# LED.net
KiCad netlist of a schematic drawn in EAGLE
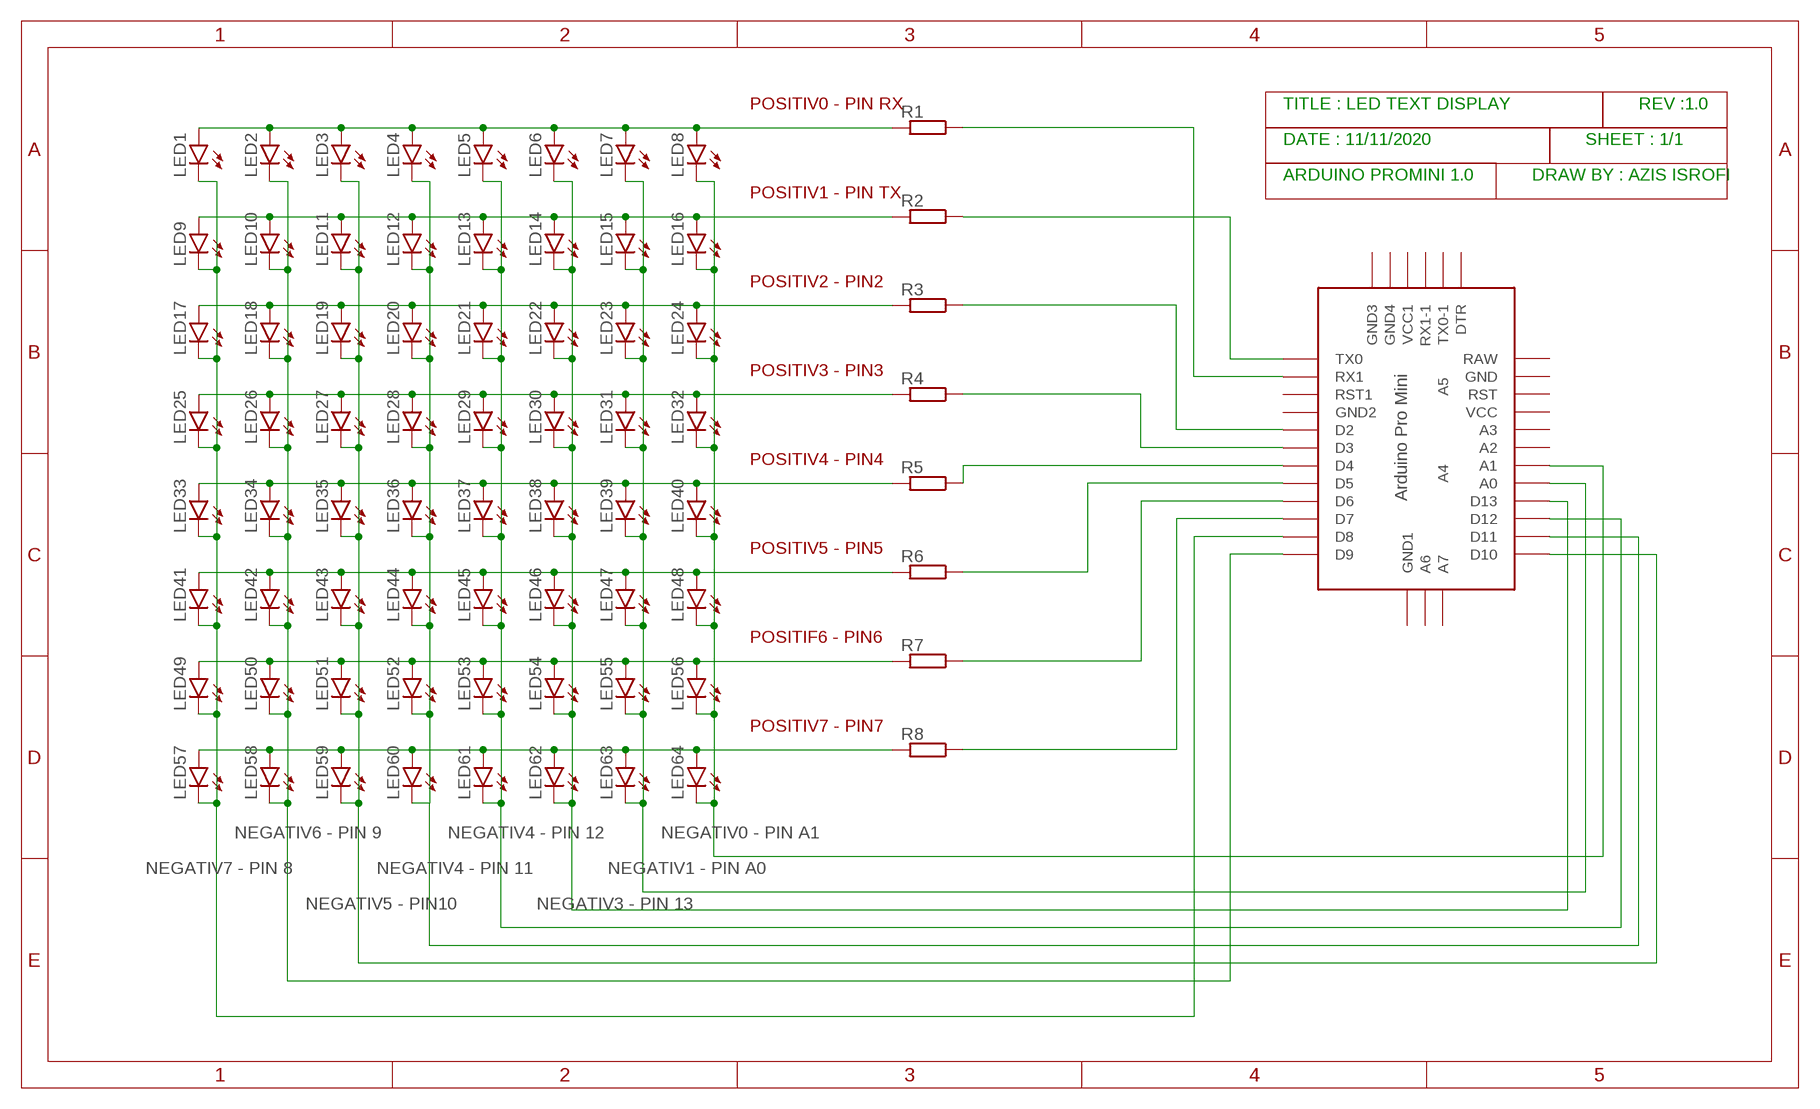
[diagram p0: schematic, sheet 1]

(export (version "E")
  (design (tool "Eeschema 10.0.6"))
  (components
    (comp (ref "LED1")
      (value "LED")
      (footprint "eagle-import:SMARTLED-TTW")
      (libsource (lib "eagle-import") (part "LED"))
    )
    (comp (ref "LED2")
      (value "LED")
      (footprint "eagle-import:SMARTLED-TTW")
      (libsource (lib "eagle-import") (part "LED"))
    )
    (comp (ref "LED3")
      (value "LED")
      (footprint "eagle-import:SMARTLED-TTW")
      (libsource (lib "eagle-import") (part "LED"))
    )
    (comp (ref "LED4")
      (value "LED")
      (footprint "eagle-import:SMARTLED-TTW")
      (libsource (lib "eagle-import") (part "LED"))
    )
    (comp (ref "LED5")
      (value "LED")
      (footprint "eagle-import:SMARTLED-TTW")
      (libsource (lib "eagle-import") (part "LED"))
    )
    (comp (ref "LED6")
      (value "LED")
      (footprint "eagle-import:SMARTLED-TTW")
      (libsource (lib "eagle-import") (part "LED"))
    )
    (comp (ref "LED7")
      (value "LED")
      (footprint "eagle-import:SMARTLED-TTW")
      (libsource (lib "eagle-import") (part "LED"))
    )
    (comp (ref "LED8")
      (value "LED")
      (footprint "eagle-import:SMARTLED-TTW")
      (libsource (lib "eagle-import") (part "LED"))
    )
    (comp (ref "LED9")
      (value "LED")
      (footprint "eagle-import:SMARTLED-TTW")
      (libsource (lib "eagle-import") (part "LED"))
    )
    (comp (ref "LED10")
      (value "LED")
      (footprint "eagle-import:SMARTLED-TTW")
      (libsource (lib "eagle-import") (part "LED"))
    )
    (comp (ref "LED11")
      (value "LED")
      (footprint "eagle-import:SMARTLED-TTW")
      (libsource (lib "eagle-import") (part "LED"))
    )
    (comp (ref "LED12")
      (value "LED")
      (footprint "eagle-import:SMARTLED-TTW")
      (libsource (lib "eagle-import") (part "LED"))
    )
    (comp (ref "LED13")
      (value "LED")
      (footprint "eagle-import:SMARTLED-TTW")
      (libsource (lib "eagle-import") (part "LED"))
    )
    (comp (ref "LED14")
      (value "LED")
      (footprint "eagle-import:SMARTLED-TTW")
      (libsource (lib "eagle-import") (part "LED"))
    )
    (comp (ref "LED15")
      (value "LED")
      (footprint "eagle-import:SMARTLED-TTW")
      (libsource (lib "eagle-import") (part "LED"))
    )
    (comp (ref "LED16")
      (value "LED")
      (footprint "eagle-import:SMARTLED-TTW")
      (libsource (lib "eagle-import") (part "LED"))
    )
    (comp (ref "LED17")
      (value "LED")
      (footprint "eagle-import:SMARTLED-TTW")
      (libsource (lib "eagle-import") (part "LED"))
    )
    (comp (ref "LED18")
      (value "LED")
      (footprint "eagle-import:SMARTLED-TTW")
      (libsource (lib "eagle-import") (part "LED"))
    )
    (comp (ref "LED19")
      (value "LED")
      (footprint "eagle-import:SMARTLED-TTW")
      (libsource (lib "eagle-import") (part "LED"))
    )
    (comp (ref "LED20")
      (value "LED")
      (footprint "eagle-import:SMARTLED-TTW")
      (libsource (lib "eagle-import") (part "LED"))
    )
    (comp (ref "LED21")
      (value "LED")
      (footprint "eagle-import:SMARTLED-TTW")
      (libsource (lib "eagle-import") (part "LED"))
    )
    (comp (ref "LED22")
      (value "LED")
      (footprint "eagle-import:SMARTLED-TTW")
      (libsource (lib "eagle-import") (part "LED"))
    )
    (comp (ref "LED23")
      (value "LED")
      (footprint "eagle-import:SMARTLED-TTW")
      (libsource (lib "eagle-import") (part "LED"))
    )
    (comp (ref "LED24")
      (value "LED")
      (footprint "eagle-import:SMARTLED-TTW")
      (libsource (lib "eagle-import") (part "LED"))
    )
    (comp (ref "LED25")
      (value "LED")
      (footprint "eagle-import:SMARTLED-TTW")
      (libsource (lib "eagle-import") (part "LED"))
    )
    (comp (ref "LED26")
      (value "LED")
      (footprint "eagle-import:SMARTLED-TTW")
      (libsource (lib "eagle-import") (part "LED"))
    )
    (comp (ref "LED27")
      (value "LED")
      (footprint "eagle-import:SMARTLED-TTW")
      (libsource (lib "eagle-import") (part "LED"))
    )
    (comp (ref "LED28")
      (value "LED")
      (footprint "eagle-import:SMARTLED-TTW")
      (libsource (lib "eagle-import") (part "LED"))
    )
    (comp (ref "LED29")
      (value "LED")
      (footprint "eagle-import:SMARTLED-TTW")
      (libsource (lib "eagle-import") (part "LED"))
    )
    (comp (ref "LED30")
      (value "LED")
      (footprint "eagle-import:SMARTLED-TTW")
      (libsource (lib "eagle-import") (part "LED"))
    )
    (comp (ref "LED31")
      (value "LED")
      (footprint "eagle-import:SMARTLED-TTW")
      (libsource (lib "eagle-import") (part "LED"))
    )
    (comp (ref "LED32")
      (value "LED")
      (footprint "eagle-import:SMARTLED-TTW")
      (libsource (lib "eagle-import") (part "LED"))
    )
    (comp (ref "LED33")
      (value "LED")
      (footprint "eagle-import:SMARTLED-TTW")
      (libsource (lib "eagle-import") (part "LED"))
    )
    (comp (ref "LED34")
      (value "LED")
      (footprint "eagle-import:SMARTLED-TTW")
      (libsource (lib "eagle-import") (part "LED"))
    )
    (comp (ref "LED35")
      (value "LED")
      (footprint "eagle-import:SMARTLED-TTW")
      (libsource (lib "eagle-import") (part "LED"))
    )
    (comp (ref "LED36")
      (value "LED")
      (footprint "eagle-import:SMARTLED-TTW")
      (libsource (lib "eagle-import") (part "LED"))
    )
    (comp (ref "LED37")
      (value "LED")
      (footprint "eagle-import:SMARTLED-TTW")
      (libsource (lib "eagle-import") (part "LED"))
    )
    (comp (ref "LED38")
      (value "LED")
      (footprint "eagle-import:SMARTLED-TTW")
      (libsource (lib "eagle-import") (part "LED"))
    )
    (comp (ref "LED39")
      (value "LED")
      (footprint "eagle-import:SMARTLED-TTW")
      (libsource (lib "eagle-import") (part "LED"))
    )
    (comp (ref "LED40")
      (value "LED")
      (footprint "eagle-import:SMARTLED-TTW")
      (libsource (lib "eagle-import") (part "LED"))
    )
    (comp (ref "LED41")
      (value "LED")
      (footprint "eagle-import:SMARTLED-TTW")
      (libsource (lib "eagle-import") (part "LED"))
    )
    (comp (ref "LED42")
      (value "LED")
      (footprint "eagle-import:SMARTLED-TTW")
      (libsource (lib "eagle-import") (part "LED"))
    )
    (comp (ref "LED43")
      (value "LED")
      (footprint "eagle-import:SMARTLED-TTW")
      (libsource (lib "eagle-import") (part "LED"))
    )
    (comp (ref "LED44")
      (value "LED")
      (footprint "eagle-import:SMARTLED-TTW")
      (libsource (lib "eagle-import") (part "LED"))
    )
    (comp (ref "LED45")
      (value "LED")
      (footprint "eagle-import:SMARTLED-TTW")
      (libsource (lib "eagle-import") (part "LED"))
    )
    (comp (ref "LED46")
      (value "LED")
      (footprint "eagle-import:SMARTLED-TTW")
      (libsource (lib "eagle-import") (part "LED"))
    )
    (comp (ref "LED47")
      (value "LED")
      (footprint "eagle-import:SMARTLED-TTW")
      (libsource (lib "eagle-import") (part "LED"))
    )
    (comp (ref "LED48")
      (value "LED")
      (footprint "eagle-import:SMARTLED-TTW")
      (libsource (lib "eagle-import") (part "LED"))
    )
    (comp (ref "LED49")
      (value "LED")
      (footprint "eagle-import:SMARTLED-TTW")
      (libsource (lib "eagle-import") (part "LED"))
    )
    (comp (ref "LED50")
      (value "LED")
      (footprint "eagle-import:SMARTLED-TTW")
      (libsource (lib "eagle-import") (part "LED"))
    )
    (comp (ref "LED51")
      (value "LED")
      (footprint "eagle-import:SMARTLED-TTW")
      (libsource (lib "eagle-import") (part "LED"))
    )
    (comp (ref "LED52")
      (value "LED")
      (footprint "eagle-import:SMARTLED-TTW")
      (libsource (lib "eagle-import") (part "LED"))
    )
    (comp (ref "LED53")
      (value "LED")
      (footprint "eagle-import:SMARTLED-TTW")
      (libsource (lib "eagle-import") (part "LED"))
    )
    (comp (ref "LED54")
      (value "LED")
      (footprint "eagle-import:SMARTLED-TTW")
      (libsource (lib "eagle-import") (part "LED"))
    )
    (comp (ref "LED55")
      (value "LED")
      (footprint "eagle-import:SMARTLED-TTW")
      (libsource (lib "eagle-import") (part "LED"))
    )
    (comp (ref "LED56")
      (value "LED")
      (footprint "eagle-import:SMARTLED-TTW")
      (libsource (lib "eagle-import") (part "LED"))
    )
    (comp (ref "LED57")
      (value "LED")
      (footprint "eagle-import:SMARTLED-TTW")
      (libsource (lib "eagle-import") (part "LED"))
    )
    (comp (ref "LED58")
      (value "LED")
      (footprint "eagle-import:SMARTLED-TTW")
      (libsource (lib "eagle-import") (part "LED"))
    )
    (comp (ref "LED59")
      (value "LED")
      (footprint "eagle-import:SMARTLED-TTW")
      (libsource (lib "eagle-import") (part "LED"))
    )
    (comp (ref "LED60")
      (value "LED")
      (footprint "eagle-import:SMARTLED-TTW")
      (libsource (lib "eagle-import") (part "LED"))
    )
    (comp (ref "LED61")
      (value "LED")
      (footprint "eagle-import:SMARTLED-TTW")
      (libsource (lib "eagle-import") (part "LED"))
    )
    (comp (ref "LED62")
      (value "LED")
      (footprint "eagle-import:SMARTLED-TTW")
      (libsource (lib "eagle-import") (part "LED"))
    )
    (comp (ref "LED63")
      (value "LED")
      (footprint "eagle-import:SMARTLED-TTW")
      (libsource (lib "eagle-import") (part "LED"))
    )
    (comp (ref "LED64")
      (value "LED")
      (footprint "eagle-import:SMARTLED-TTW")
      (libsource (lib "eagle-import") (part "LED"))
    )
    (comp (ref "R1")
      (value "BVS")
      (footprint "eagle-import:BVS")
      (libsource (lib "eagle-import") (part "BVS"))
    )
    (comp (ref "R2")
      (value "BVS")
      (footprint "eagle-import:BVS")
      (libsource (lib "eagle-import") (part "BVS"))
    )
    (comp (ref "R3")
      (value "BVS")
      (footprint "eagle-import:BVS")
      (libsource (lib "eagle-import") (part "BVS"))
    )
    (comp (ref "R4")
      (value "BVS")
      (footprint "eagle-import:BVS")
      (libsource (lib "eagle-import") (part "BVS"))
    )
    (comp (ref "R5")
      (value "BVS")
      (footprint "eagle-import:BVS")
      (libsource (lib "eagle-import") (part "BVS"))
    )
    (comp (ref "R6")
      (value "BVS")
      (footprint "eagle-import:BVS")
      (libsource (lib "eagle-import") (part "BVS"))
    )
    (comp (ref "R7")
      (value "BVS")
      (footprint "eagle-import:BVS")
      (libsource (lib "eagle-import") (part "BVS"))
    )
    (comp (ref "R8")
      (value "BVS")
      (footprint "eagle-import:BVS")
      (libsource (lib "eagle-import") (part "BVS"))
    )
    (comp (ref "U$1")
      (value "ABK-PRO-MINI")
      (footprint "eagle-import:ABK-PRO-MINI")
      (libsource (lib "eagle-import") (part "ABK-PRO-MINI"))
    )
  )
  (nets
    (net (code "1") (name "Net-(LED1-A)") (class "Default")
      (node (ref "LED1") (pin "A@1") (pinfunction "A_A@1") (pintype "passive"))
      (node (ref "LED2") (pin "A@1") (pinfunction "A_A@1") (pintype "passive"))
      (node (ref "LED3") (pin "A@1") (pinfunction "A_A@1") (pintype "passive"))
      (node (ref "LED4") (pin "A@1") (pinfunction "A_A@1") (pintype "passive"))
      (node (ref "LED5") (pin "A@1") (pinfunction "A_A@1") (pintype "passive"))
      (node (ref "LED6") (pin "A@1") (pinfunction "A_A@1") (pintype "passive"))
      (node (ref "LED7") (pin "A@1") (pinfunction "A_A@1") (pintype "passive"))
      (node (ref "LED8") (pin "A@1") (pinfunction "A_A@1") (pintype "passive"))
      (node (ref "R1") (pin "2") (pinfunction "2_2") (pintype "passive"))
    )
    (net (code "2") (name "Net-(LED1-C)") (class "Default")
      (node (ref "LED1") (pin "C@1") (pinfunction "C_C@1") (pintype "passive"))
      (node (ref "LED17") (pin "C@1") (pinfunction "C_C@1") (pintype "passive"))
      (node (ref "LED25") (pin "C@1") (pinfunction "C_C@1") (pintype "passive"))
      (node (ref "LED33") (pin "C@1") (pinfunction "C_C@1") (pintype "passive"))
      (node (ref "LED41") (pin "C@1") (pinfunction "C_C@1") (pintype "passive"))
      (node (ref "LED49") (pin "C@1") (pinfunction "C_C@1") (pintype "passive"))
      (node (ref "LED57") (pin "C@1") (pinfunction "C_C@1") (pintype "passive"))
      (node (ref "LED9") (pin "C@1") (pinfunction "C_C@1") (pintype "passive"))
      (node (ref "U$1") (pin "D8") (pinfunction "D8_D8") (pintype "bidirectional"))
    )
    (net (code "3") (name "Net-(LED10-A)") (class "Default")
      (node (ref "LED10") (pin "A@1") (pinfunction "A_A@1") (pintype "passive"))
      (node (ref "LED11") (pin "A@1") (pinfunction "A_A@1") (pintype "passive"))
      (node (ref "LED12") (pin "A@1") (pinfunction "A_A@1") (pintype "passive"))
      (node (ref "LED13") (pin "A@1") (pinfunction "A_A@1") (pintype "passive"))
      (node (ref "LED14") (pin "A@1") (pinfunction "A_A@1") (pintype "passive"))
      (node (ref "LED15") (pin "A@1") (pinfunction "A_A@1") (pintype "passive"))
      (node (ref "LED16") (pin "A@1") (pinfunction "A_A@1") (pintype "passive"))
      (node (ref "LED9") (pin "A@1") (pinfunction "A_A@1") (pintype "passive"))
      (node (ref "R2") (pin "2") (pinfunction "2_2") (pintype "passive"))
    )
    (net (code "4") (name "Net-(LED10-C)") (class "Default")
      (node (ref "LED10") (pin "C@1") (pinfunction "C_C@1") (pintype "passive"))
      (node (ref "LED18") (pin "C@1") (pinfunction "C_C@1") (pintype "passive"))
      (node (ref "LED2") (pin "C@1") (pinfunction "C_C@1") (pintype "passive"))
      (node (ref "LED26") (pin "C@1") (pinfunction "C_C@1") (pintype "passive"))
      (node (ref "LED34") (pin "C@1") (pinfunction "C_C@1") (pintype "passive"))
      (node (ref "LED42") (pin "C@1") (pinfunction "C_C@1") (pintype "passive"))
      (node (ref "LED50") (pin "C@1") (pinfunction "C_C@1") (pintype "passive"))
      (node (ref "LED58") (pin "C@1") (pinfunction "C_C@1") (pintype "passive"))
      (node (ref "U$1") (pin "D9") (pinfunction "D9_D9") (pintype "bidirectional"))
    )
    (net (code "5") (name "Net-(LED11-C)") (class "Default")
      (node (ref "LED11") (pin "C@1") (pinfunction "C_C@1") (pintype "passive"))
      (node (ref "LED19") (pin "C@1") (pinfunction "C_C@1") (pintype "passive"))
      (node (ref "LED27") (pin "C@1") (pinfunction "C_C@1") (pintype "passive"))
      (node (ref "LED3") (pin "C@1") (pinfunction "C_C@1") (pintype "passive"))
      (node (ref "LED35") (pin "C@1") (pinfunction "C_C@1") (pintype "passive"))
      (node (ref "LED43") (pin "C@1") (pinfunction "C_C@1") (pintype "passive"))
      (node (ref "LED51") (pin "C@1") (pinfunction "C_C@1") (pintype "passive"))
      (node (ref "LED59") (pin "C@1") (pinfunction "C_C@1") (pintype "passive"))
      (node (ref "U$1") (pin "D10") (pinfunction "D10_D10") (pintype "bidirectional"))
    )
    (net (code "6") (name "Net-(LED12-C)") (class "Default")
      (node (ref "LED12") (pin "C@1") (pinfunction "C_C@1") (pintype "passive"))
      (node (ref "LED20") (pin "C@1") (pinfunction "C_C@1") (pintype "passive"))
      (node (ref "LED28") (pin "C@1") (pinfunction "C_C@1") (pintype "passive"))
      (node (ref "LED36") (pin "C@1") (pinfunction "C_C@1") (pintype "passive"))
      (node (ref "LED4") (pin "C@1") (pinfunction "C_C@1") (pintype "passive"))
      (node (ref "LED44") (pin "C@1") (pinfunction "C_C@1") (pintype "passive"))
      (node (ref "LED52") (pin "C@1") (pinfunction "C_C@1") (pintype "passive"))
      (node (ref "LED60") (pin "C@1") (pinfunction "C_C@1") (pintype "passive"))
      (node (ref "U$1") (pin "D11") (pinfunction "D11_D11") (pintype "bidirectional"))
    )
    (net (code "7") (name "Net-(LED13-C)") (class "Default")
      (node (ref "LED13") (pin "C@1") (pinfunction "C_C@1") (pintype "passive"))
      (node (ref "LED21") (pin "C@1") (pinfunction "C_C@1") (pintype "passive"))
      (node (ref "LED29") (pin "C@1") (pinfunction "C_C@1") (pintype "passive"))
      (node (ref "LED37") (pin "C@1") (pinfunction "C_C@1") (pintype "passive"))
      (node (ref "LED45") (pin "C@1") (pinfunction "C_C@1") (pintype "passive"))
      (node (ref "LED5") (pin "C@1") (pinfunction "C_C@1") (pintype "passive"))
      (node (ref "LED53") (pin "C@1") (pinfunction "C_C@1") (pintype "passive"))
      (node (ref "LED61") (pin "C@1") (pinfunction "C_C@1") (pintype "passive"))
      (node (ref "U$1") (pin "D12") (pinfunction "D12_D12") (pintype "bidirectional"))
    )
    (net (code "8") (name "Net-(LED14-C)") (class "Default")
      (node (ref "LED14") (pin "C@1") (pinfunction "C_C@1") (pintype "passive"))
      (node (ref "LED22") (pin "C@1") (pinfunction "C_C@1") (pintype "passive"))
      (node (ref "LED30") (pin "C@1") (pinfunction "C_C@1") (pintype "passive"))
      (node (ref "LED38") (pin "C@1") (pinfunction "C_C@1") (pintype "passive"))
      (node (ref "LED46") (pin "C@1") (pinfunction "C_C@1") (pintype "passive"))
      (node (ref "LED54") (pin "C@1") (pinfunction "C_C@1") (pintype "passive"))
      (node (ref "LED6") (pin "C@1") (pinfunction "C_C@1") (pintype "passive"))
      (node (ref "LED62") (pin "C@1") (pinfunction "C_C@1") (pintype "passive"))
      (node (ref "U$1") (pin "D13") (pinfunction "D13_D13") (pintype "bidirectional"))
    )
    (net (code "9") (name "Net-(LED15-C)") (class "Default")
      (node (ref "LED15") (pin "C@1") (pinfunction "C_C@1") (pintype "passive"))
      (node (ref "LED23") (pin "C@1") (pinfunction "C_C@1") (pintype "passive"))
      (node (ref "LED31") (pin "C@1") (pinfunction "C_C@1") (pintype "passive"))
      (node (ref "LED39") (pin "C@1") (pinfunction "C_C@1") (pintype "passive"))
      (node (ref "LED47") (pin "C@1") (pinfunction "C_C@1") (pintype "passive"))
      (node (ref "LED55") (pin "C@1") (pinfunction "C_C@1") (pintype "passive"))
      (node (ref "LED63") (pin "C@1") (pinfunction "C_C@1") (pintype "passive"))
      (node (ref "LED7") (pin "C@1") (pinfunction "C_C@1") (pintype "passive"))
      (node (ref "U$1") (pin "A0") (pinfunction "A0_A0") (pintype "bidirectional"))
    )
    (net (code "10") (name "Net-(LED16-C)") (class "Default")
      (node (ref "LED16") (pin "C@1") (pinfunction "C_C@1") (pintype "passive"))
      (node (ref "LED24") (pin "C@1") (pinfunction "C_C@1") (pintype "passive"))
      (node (ref "LED32") (pin "C@1") (pinfunction "C_C@1") (pintype "passive"))
      (node (ref "LED40") (pin "C@1") (pinfunction "C_C@1") (pintype "passive"))
      (node (ref "LED48") (pin "C@1") (pinfunction "C_C@1") (pintype "passive"))
      (node (ref "LED56") (pin "C@1") (pinfunction "C_C@1") (pintype "passive"))
      (node (ref "LED64") (pin "C@1") (pinfunction "C_C@1") (pintype "passive"))
      (node (ref "LED8") (pin "C@1") (pinfunction "C_C@1") (pintype "passive"))
      (node (ref "U$1") (pin "A1") (pinfunction "A1_A1") (pintype "bidirectional"))
    )
    (net (code "11") (name "Net-(LED17-A)") (class "Default")
      (node (ref "LED17") (pin "A@1") (pinfunction "A_A@1") (pintype "passive"))
      (node (ref "LED18") (pin "A@1") (pinfunction "A_A@1") (pintype "passive"))
      (node (ref "LED19") (pin "A@1") (pinfunction "A_A@1") (pintype "passive"))
      (node (ref "LED20") (pin "A@1") (pinfunction "A_A@1") (pintype "passive"))
      (node (ref "LED21") (pin "A@1") (pinfunction "A_A@1") (pintype "passive"))
      (node (ref "LED22") (pin "A@1") (pinfunction "A_A@1") (pintype "passive"))
      (node (ref "LED23") (pin "A@1") (pinfunction "A_A@1") (pintype "passive"))
      (node (ref "LED24") (pin "A@1") (pinfunction "A_A@1") (pintype "passive"))
      (node (ref "R3") (pin "2") (pinfunction "2_2") (pintype "passive"))
    )
    (net (code "12") (name "Net-(LED25-A)") (class "Default")
      (node (ref "LED25") (pin "A@1") (pinfunction "A_A@1") (pintype "passive"))
      (node (ref "LED26") (pin "A@1") (pinfunction "A_A@1") (pintype "passive"))
      (node (ref "LED27") (pin "A@1") (pinfunction "A_A@1") (pintype "passive"))
      (node (ref "LED28") (pin "A@1") (pinfunction "A_A@1") (pintype "passive"))
      (node (ref "LED29") (pin "A@1") (pinfunction "A_A@1") (pintype "passive"))
      (node (ref "LED30") (pin "A@1") (pinfunction "A_A@1") (pintype "passive"))
      (node (ref "LED31") (pin "A@1") (pinfunction "A_A@1") (pintype "passive"))
      (node (ref "LED32") (pin "A@1") (pinfunction "A_A@1") (pintype "passive"))
      (node (ref "R4") (pin "2") (pinfunction "2_2") (pintype "passive"))
    )
    (net (code "13") (name "Net-(LED33-A)") (class "Default")
      (node (ref "LED33") (pin "A@1") (pinfunction "A_A@1") (pintype "passive"))
      (node (ref "LED34") (pin "A@1") (pinfunction "A_A@1") (pintype "passive"))
      (node (ref "LED35") (pin "A@1") (pinfunction "A_A@1") (pintype "passive"))
      (node (ref "LED36") (pin "A@1") (pinfunction "A_A@1") (pintype "passive"))
      (node (ref "LED37") (pin "A@1") (pinfunction "A_A@1") (pintype "passive"))
      (node (ref "LED38") (pin "A@1") (pinfunction "A_A@1") (pintype "passive"))
      (node (ref "LED39") (pin "A@1") (pinfunction "A_A@1") (pintype "passive"))
      (node (ref "LED40") (pin "A@1") (pinfunction "A_A@1") (pintype "passive"))
      (node (ref "R5") (pin "2") (pinfunction "2_2") (pintype "passive"))
    )
    (net (code "14") (name "Net-(LED41-A)") (class "Default")
      (node (ref "LED41") (pin "A@1") (pinfunction "A_A@1") (pintype "passive"))
      (node (ref "LED42") (pin "A@1") (pinfunction "A_A@1") (pintype "passive"))
      (node (ref "LED43") (pin "A@1") (pinfunction "A_A@1") (pintype "passive"))
      (node (ref "LED44") (pin "A@1") (pinfunction "A_A@1") (pintype "passive"))
      (node (ref "LED45") (pin "A@1") (pinfunction "A_A@1") (pintype "passive"))
      (node (ref "LED46") (pin "A@1") (pinfunction "A_A@1") (pintype "passive"))
      (node (ref "LED47") (pin "A@1") (pinfunction "A_A@1") (pintype "passive"))
      (node (ref "LED48") (pin "A@1") (pinfunction "A_A@1") (pintype "passive"))
      (node (ref "R6") (pin "2") (pinfunction "2_2") (pintype "passive"))
    )
    (net (code "15") (name "Net-(LED49-A)") (class "Default")
      (node (ref "LED49") (pin "A@1") (pinfunction "A_A@1") (pintype "passive"))
      (node (ref "LED50") (pin "A@1") (pinfunction "A_A@1") (pintype "passive"))
      (node (ref "LED51") (pin "A@1") (pinfunction "A_A@1") (pintype "passive"))
      (node (ref "LED52") (pin "A@1") (pinfunction "A_A@1") (pintype "passive"))
      (node (ref "LED53") (pin "A@1") (pinfunction "A_A@1") (pintype "passive"))
      (node (ref "LED54") (pin "A@1") (pinfunction "A_A@1") (pintype "passive"))
      (node (ref "LED55") (pin "A@1") (pinfunction "A_A@1") (pintype "passive"))
      (node (ref "LED56") (pin "A@1") (pinfunction "A_A@1") (pintype "passive"))
      (node (ref "R7") (pin "2") (pinfunction "2_2") (pintype "passive"))
    )
    (net (code "16") (name "Net-(LED57-A)") (class "Default")
      (node (ref "LED57") (pin "A@1") (pinfunction "A_A@1") (pintype "passive"))
      (node (ref "LED58") (pin "A@1") (pinfunction "A_A@1") (pintype "passive"))
      (node (ref "LED59") (pin "A@1") (pinfunction "A_A@1") (pintype "passive"))
      (node (ref "LED60") (pin "A@1") (pinfunction "A_A@1") (pintype "passive"))
      (node (ref "LED61") (pin "A@1") (pinfunction "A_A@1") (pintype "passive"))
      (node (ref "LED62") (pin "A@1") (pinfunction "A_A@1") (pintype "passive"))
      (node (ref "LED63") (pin "A@1") (pinfunction "A_A@1") (pintype "passive"))
      (node (ref "LED64") (pin "A@1") (pinfunction "A_A@1") (pintype "passive"))
      (node (ref "R8") (pin "2") (pinfunction "2_2") (pintype "passive"))
    )
    (net (code "17") (name "Net-(R1-Pad1)") (class "Default")
      (node (ref "R1") (pin "1") (pinfunction "1_1") (pintype "passive"))
      (node (ref "U$1") (pin "RX1") (pinfunction "RX1_RX1") (pintype "bidirectional"))
    )
    (net (code "18") (name "Net-(R2-Pad1)") (class "Default")
      (node (ref "R2") (pin "1") (pinfunction "1_1") (pintype "passive"))
      (node (ref "U$1") (pin "TX0") (pinfunction "TX0_TX0") (pintype "bidirectional"))
    )
    (net (code "19") (name "Net-(R3-Pad1)") (class "Default")
      (node (ref "R3") (pin "1") (pinfunction "1_1") (pintype "passive"))
      (node (ref "U$1") (pin "D2") (pinfunction "D2_D2") (pintype "bidirectional"))
    )
    (net (code "20") (name "Net-(R4-Pad1)") (class "Default")
      (node (ref "R4") (pin "1") (pinfunction "1_1") (pintype "passive"))
      (node (ref "U$1") (pin "D3") (pinfunction "D3_D3") (pintype "bidirectional"))
    )
    (net (code "21") (name "Net-(R5-Pad1)") (class "Default")
      (node (ref "R5") (pin "1") (pinfunction "1_1") (pintype "passive"))
      (node (ref "U$1") (pin "D4") (pinfunction "D4_D4") (pintype "bidirectional"))
    )
    (net (code "22") (name "Net-(R6-Pad1)") (class "Default")
      (node (ref "R6") (pin "1") (pinfunction "1_1") (pintype "passive"))
      (node (ref "U$1") (pin "D5") (pinfunction "D5_D5") (pintype "bidirectional"))
    )
    (net (code "23") (name "Net-(R7-Pad1)") (class "Default")
      (node (ref "R7") (pin "1") (pinfunction "1_1") (pintype "passive"))
      (node (ref "U$1") (pin "D6") (pinfunction "D6_D6") (pintype "bidirectional"))
    )
    (net (code "24") (name "Net-(R8-Pad1)") (class "Default")
      (node (ref "R8") (pin "1") (pinfunction "1_1") (pintype "passive"))
      (node (ref "U$1") (pin "D7") (pinfunction "D7_D7") (pintype "bidirectional"))
    )
    (net (code "25") (name "unconnected-(U$1-GND1-PadGND4)") (class "Default")
      (node (ref "U$1") (pin "GND4") (pinfunction "GND1_GND4") (pintype "bidirectional"))
    )
    (net (code "26") (name "unconnected-(U$1-GND2-PadGND1)") (class "Default")
      (node (ref "U$1") (pin "GND1") (pinfunction "GND2_GND1") (pintype "bidirectional"))
    )
    (net (code "27") (name "unconnected-(U$1-GND3-PadGND2)") (class "Default")
      (node (ref "U$1") (pin "GND2") (pinfunction "GND3_GND2") (pintype "bidirectional"))
    )
    (net (code "28") (name "unconnected-(U$1-GND4-PadGND3)") (class "Default")
      (node (ref "U$1") (pin "GND3") (pinfunction "GND4_GND3") (pintype "bidirectional"))
    )
    (net (code "29") (name "unconnected-(U$1-PadA2)") (class "Default")
      (node (ref "U$1") (pin "A2") (pinfunction "A2_A2") (pintype "bidirectional"))
    )
    (net (code "30") (name "unconnected-(U$1-PadA3)") (class "Default")
      (node (ref "U$1") (pin "A3") (pinfunction "A3_A3") (pintype "bidirectional"))
    )
    (net (code "31") (name "unconnected-(U$1-PadA4)") (class "Default")
      (node (ref "U$1") (pin "A4") (pinfunction "A4_A4") (pintype "bidirectional"))
    )
    (net (code "32") (name "unconnected-(U$1-PadA5)") (class "Default")
      (node (ref "U$1") (pin "A5") (pinfunction "A5_A5") (pintype "bidirectional"))
    )
    (net (code "33") (name "unconnected-(U$1-PadA6)") (class "Default")
      (node (ref "U$1") (pin "A6") (pinfunction "A6_A6") (pintype "bidirectional"))
    )
    (net (code "34") (name "unconnected-(U$1-PadA7)") (class "Default")
      (node (ref "U$1") (pin "A7") (pinfunction "A7_A7") (pintype "bidirectional"))
    )
    (net (code "35") (name "unconnected-(U$1-PadDTR)") (class "Default")
      (node (ref "U$1") (pin "DTR") (pinfunction "DTR_DTR") (pintype "bidirectional"))
    )
    (net (code "36") (name "unconnected-(U$1-PadGND)") (class "Default")
      (node (ref "U$1") (pin "GND") (pinfunction "GND_GND") (pintype "bidirectional"))
    )
    (net (code "37") (name "unconnected-(U$1-PadRAW)") (class "Default")
      (node (ref "U$1") (pin "RAW") (pinfunction "RAW_RAW") (pintype "bidirectional"))
    )
    (net (code "38") (name "unconnected-(U$1-PadRST)") (class "Default")
      (node (ref "U$1") (pin "RST") (pinfunction "RST_RST") (pintype "bidirectional"))
    )
    (net (code "39") (name "unconnected-(U$1-PadRST1)") (class "Default")
      (node (ref "U$1") (pin "RST1") (pinfunction "RST1_RST1") (pintype "bidirectional"))
    )
    (net (code "40") (name "unconnected-(U$1-PadRX1-1)") (class "Default")
      (node (ref "U$1") (pin "RX1-1") (pinfunction "RX1-1_RX1-1") (pintype "bidirectional"))
    )
    (net (code "41") (name "unconnected-(U$1-PadTX0-1)") (class "Default")
      (node (ref "U$1") (pin "TX0-1") (pinfunction "TX0-1_TX0-1") (pintype "bidirectional"))
    )
    (net (code "42") (name "unconnected-(U$1-PadVCC)") (class "Default")
      (node (ref "U$1") (pin "VCC") (pinfunction "VCC_VCC") (pintype "bidirectional"))
    )
    (net (code "43") (name "unconnected-(U$1-PadVCC1)") (class "Default")
      (node (ref "U$1") (pin "VCC1") (pinfunction "VCC1_VCC1") (pintype "bidirectional"))
    )
  )
)
